# Schematic.net
KiCad netlist of a schematic drawn in Altium Designer
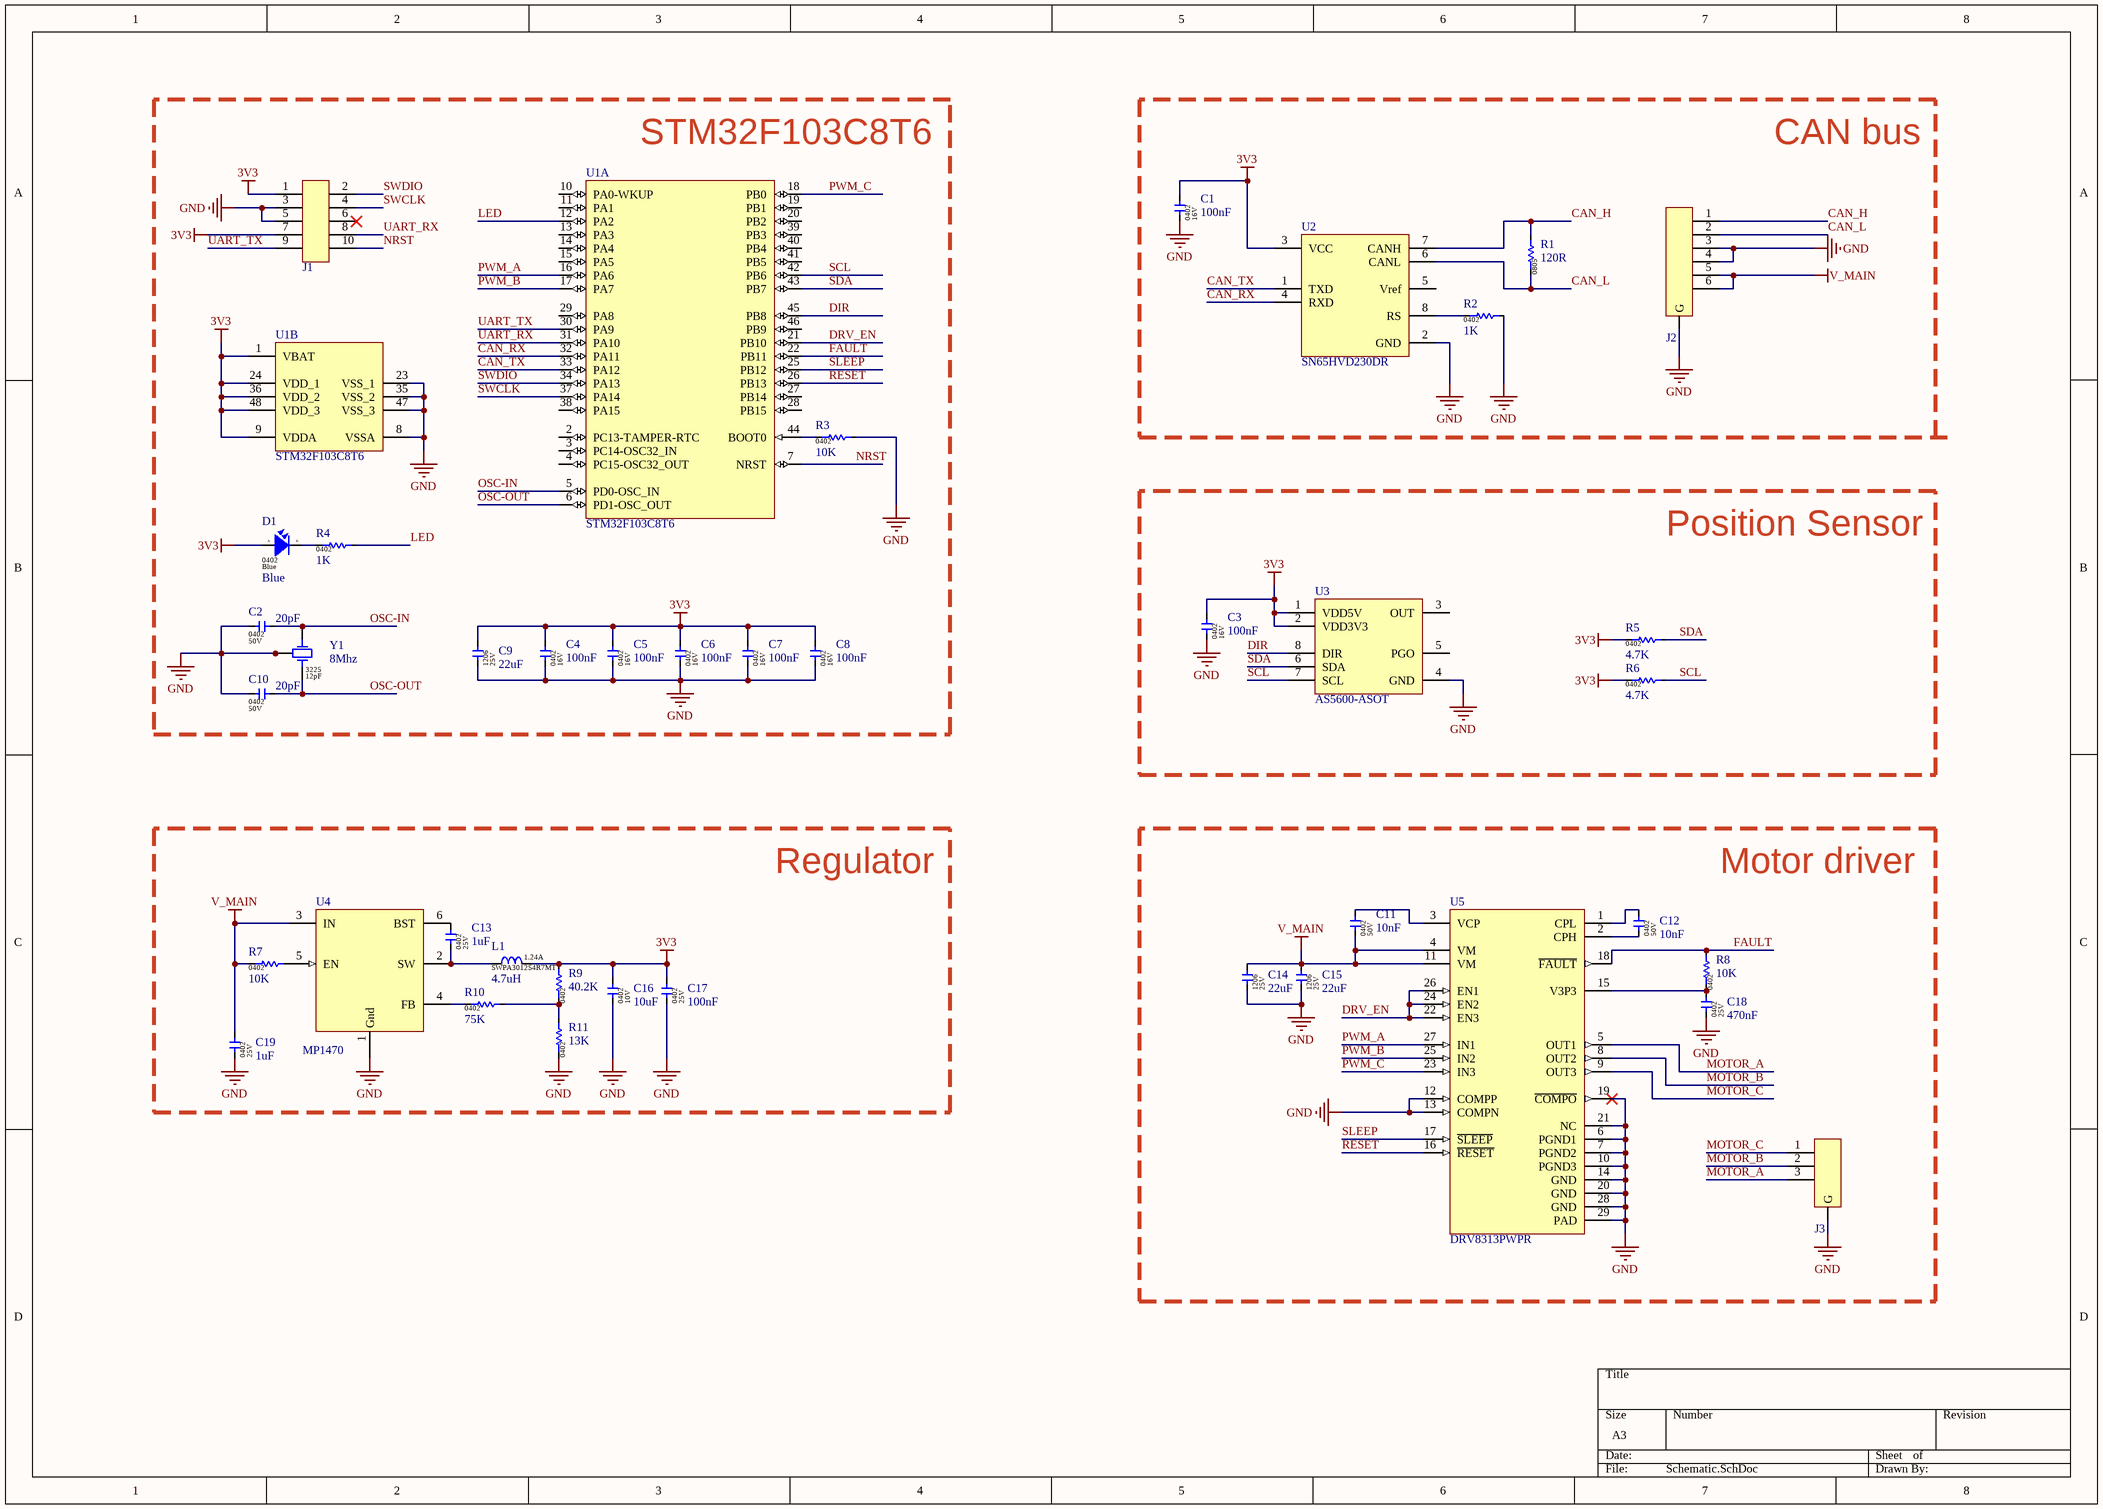
[diagram p0: Schematic.SchDoc]

(export (version "E")
  (design (tool "Eeschema 10.0.6"))
  (components
    (comp (ref "C1")
      (value "100nF")
      (footprint "CAP-0402")
      (description "100nF ±10% 16V X7R 0402 Multilayer Ceramic Capacitors MLCC - SMD/SMT RoHS")
      (fields (field (name "MANUFACTURE PART") "0402B104K160CT") (field (name "VOLTAGE") "16V"))
      (libsource (lib "Capacitor Database") (part "Cap-non-polarized"))
    )
    (comp (ref "C2")
      (value "20pF")
      (footprint "CAP-0402")
      (description "20 pF ±5% 50V Ceramic Capacitor C0G, NP0 0402 (1005 Metric)")
      (fields (field (name "MANUFACTURE PART") "CL05C200JB5NNNC") (field (name "VOLTAGE") "50V"))
      (libsource (lib "Capacitor Database") (part "Cap-non-polarized"))
    )
    (comp (ref "C3")
      (value "100nF")
      (footprint "CAP-0402")
      (description "100nF ±10% 16V X7R 0402 Multilayer Ceramic Capacitors MLCC - SMD/SMT RoHS")
      (fields (field (name "MANUFACTURE PART") "0402B104K160CT") (field (name "VOLTAGE") "16V"))
      (libsource (lib "Capacitor Database") (part "Cap-non-polarized"))
    )
    (comp (ref "C4")
      (value "100nF")
      (footprint "CAP-0402")
      (description "100nF ±10% 16V X7R 0402 Multilayer Ceramic Capacitors MLCC - SMD/SMT RoHS")
      (fields (field (name "MANUFACTURE PART") "0402B104K160CT") (field (name "VOLTAGE") "16V"))
      (libsource (lib "Capacitor Database") (part "Cap-non-polarized"))
    )
    (comp (ref "C5")
      (value "100nF")
      (footprint "CAP-0402")
      (description "100nF ±10% 16V X7R 0402 Multilayer Ceramic Capacitors MLCC - SMD/SMT RoHS")
      (fields (field (name "MANUFACTURE PART") "0402B104K160CT") (field (name "VOLTAGE") "16V"))
      (libsource (lib "Capacitor Database") (part "Cap-non-polarized"))
    )
    (comp (ref "C6")
      (value "100nF")
      (footprint "CAP-0402")
      (description "100nF ±10% 16V X7R 0402 Multilayer Ceramic Capacitors MLCC - SMD/SMT RoHS")
      (fields (field (name "MANUFACTURE PART") "0402B104K160CT") (field (name "VOLTAGE") "16V"))
      (libsource (lib "Capacitor Database") (part "Cap-non-polarized"))
    )
    (comp (ref "C7")
      (value "100nF")
      (footprint "CAP-0402")
      (description "100nF ±10% 16V X7R 0402 Multilayer Ceramic Capacitors MLCC - SMD/SMT RoHS")
      (fields (field (name "MANUFACTURE PART") "0402B104K160CT") (field (name "VOLTAGE") "16V"))
      (libsource (lib "Capacitor Database") (part "Cap-non-polarized"))
    )
    (comp (ref "C8")
      (value "100nF")
      (footprint "CAP-0402")
      (description "100nF ±10% 16V X7R 0402 Multilayer Ceramic Capacitors MLCC - SMD/SMT RoHS")
      (fields (field (name "MANUFACTURE PART") "0402B104K160CT") (field (name "VOLTAGE") "16V"))
      (libsource (lib "Capacitor Database") (part "Cap-non-polarized"))
    )
    (comp (ref "C9")
      (value "22uF")
      (footprint "CAP-1206")
      (description "X5R 25V ±10% 22uF 1206 Multilayer Ceramic Capacitors MLCC - SMD/SMT ROHS")
      (fields (field (name "MANUFACTURE PART") "CL31A226KAHNNNE") (field (name "VOLTAGE") "25V"))
      (libsource (lib "Capacitor Database") (part "Cap-non-polarized"))
    )
    (comp (ref "C10")
      (value "20pF")
      (footprint "CAP-0402")
      (description "20 pF ±5% 50V Ceramic Capacitor C0G, NP0 0402 (1005 Metric)")
      (fields (field (name "MANUFACTURE PART") "CL05C200JB5NNNC") (field (name "VOLTAGE") "50V"))
      (libsource (lib "Capacitor Database") (part "Cap-non-polarized"))
    )
    (comp (ref "C11")
      (value "10nF")
      (footprint "CAP-0402")
      (description "10nF ±5% 50V X7R 0402 Multilayer Ceramic Capacitors MLCC - SMD/SMT RoHS")
      (fields (field (name "MANUFACTURE PART") "0402B103J500CT") (field (name "VOLTAGE") "50V"))
      (libsource (lib "Capacitor Database") (part "Cap-non-polarized"))
    )
    (comp (ref "C12")
      (value "10nF")
      (footprint "CAP-0402")
      (description "10nF ±5% 50V X7R 0402 Multilayer Ceramic Capacitors MLCC - SMD/SMT RoHS")
      (fields (field (name "MANUFACTURE PART") "0402B103J500CT") (field (name "VOLTAGE") "50V"))
      (libsource (lib "Capacitor Database") (part "Cap-non-polarized"))
    )
    (comp (ref "C13")
      (value "1uF")
      (footprint "CAP-0402")
      (description "25V 1uF X5R ±10% 0402 Multilayer Ceramic Capacitors MLCC - SMD/SMT ROHS")
      (fields (field (name "MANUFACTURE PART") "0402X105K250CT") (field (name "VOLTAGE") "25V"))
      (libsource (lib "Capacitor Database") (part "Cap-non-polarized"))
    )
    (comp (ref "C14")
      (value "22uF")
      (footprint "CAP-1206")
      (description "X5R 25V ±10% 22uF 1206 Multilayer Ceramic Capacitors MLCC - SMD/SMT ROHS")
      (fields (field (name "MANUFACTURE PART") "CL31A226KAHNNNE") (field (name "VOLTAGE") "25V"))
      (libsource (lib "Capacitor Database") (part "Cap-non-polarized"))
    )
    (comp (ref "C15")
      (value "22uF")
      (footprint "CAP-1206")
      (description "X5R 25V ±10% 22uF 1206 Multilayer Ceramic Capacitors MLCC - SMD/SMT ROHS")
      (fields (field (name "MANUFACTURE PART") "CL31A226KAHNNNE") (field (name "VOLTAGE") "25V"))
      (libsource (lib "Capacitor Database") (part "Cap-non-polarized"))
    )
    (comp (ref "C16")
      (value "10uF")
      (footprint "CAP-0402")
      (description "10V 10uF X5R ±20% 0402 Multilayer Ceramic Capacitors MLCC - SMD/SMT ROHS")
      (fields (field (name "MANUFACTURE PART") "CL05A106MP5NUNC") (field (name "VOLTAGE") "10V"))
      (libsource (lib "Capacitor Database") (part "Cap-non-polarized"))
    )
    (comp (ref "C17")
      (value "100nF")
      (footprint "CAP-0402")
      (description "100nF ±10% 25V X5R 0402 Multilayer Ceramic Capacitors MLCC - SMD/SMT RoHS")
      (fields (field (name "MANUFACTURE PART") "0402X104K250CT") (field (name "VOLTAGE") "25V"))
      (libsource (lib "Capacitor Database") (part "Cap-non-polarized"))
    )
    (comp (ref "C18")
      (value "470nF")
      (footprint "CAP-0402")
      (description "470nF X5R 25V ±10% 470nF 0402 Multilayer Ceramic Capacitors MLCC - SMD/SMT ROHS")
      (fields (field (name "MANUFACTURE PART") "0402X474K250CT") (field (name "VOLTAGE") "25V"))
      (libsource (lib "Capacitor Database") (part "Cap-non-polarized"))
    )
    (comp (ref "C19")
      (value "1uF")
      (footprint "CAP-0402")
      (description "25V 1uF X5R ±10% 0402 Multilayer Ceramic Capacitors MLCC - SMD/SMT ROHS")
      (fields (field (name "MANUFACTURE PART") "0402X105K250CT") (field (name "VOLTAGE") "25V"))
      (libsource (lib "Capacitor Database") (part "Cap-non-polarized"))
    )
    (comp (ref "D1")
      (value "Blue")
      (footprint "LED-0402 BLUE")
      (description "Blue 0402 Light Emitting Diodes (LED) ROHS")
      (fields (field (name "MANUFACTURE PART") "0402-blue"))
      (libsource (lib "Led Database") (part "Led"))
    )
    (comp (ref "J1")
      (value "X1270WVS-2x05B-6TV01")
      (footprint "SMD_IDC_1.27_10P")
      (description "SMD,P=1.27mm IDC Connectors ROHS")
      (libsource (lib "Connectors, Misc") (part "Conn-10P-2x5P"))
    )
    (comp (ref "J2")
      (value "1.25T-6P-WT")
      (footprint "Conn MX1.25 (6)")
      (description "MX1.25 Header Male Pin 0.049\"(1.25mm) 6 P=1.25mm Wire To Board / Wire To Wire Connector RoHS")
      (libsource (lib "Connectors, Misc") (part "Conn-6P_PAD"))
    )
    (comp (ref "J3")
      (value "1.25T-3P-WT")
      (footprint "Conn MX1.25 (3)")
      (description "MX1.25 Header Male Pin 0.049\"(1.25mm) 3 SMD,P=1.25mm Wire To Board / Wire To Wire Connector RoHS")
      (libsource (lib "Connectors, Misc") (part "Conn-3P_PAD"))
    )
    (comp (ref "L1")
      (value "4.7uH")
      (footprint "IND-3012")
      (description "Inductor 30x30x12, 4.7±20% , 1.24A")
      (fields (field (name "MANUFACTURE PART") "SWPA3012S4R7MT"))
      (libsource (lib "Inductor Database") (part "Inductor"))
    )
    (comp (ref "R1")
      (value "120R")
      (footprint "RES-0805")
      (fields (field (name "MANUFACTURE PART") "AC0805FR-7W120RL"))
      (libsource (lib "Resistor Database") (part "Resistor"))
    )
    (comp (ref "R2")
      (value "1K")
      (footprint "RES-0402")
      (description "1kΩ ±1% 1/16W ±100ppm/℃ 0402 Chip Resistor - Surface Mount RoHS")
      (fields (field (name "MANUFACTURE PART") "WR04X1001FTL"))
      (libsource (lib "Resistor Database") (part "Resistor"))
    )
    (comp (ref "R3")
      (value "10K")
      (footprint "RES-0402")
      (description "10kΩ ±1% 1/16W ±100ppm/℃ 0402 Chip Resistor - Surface Mount RoHS")
      (fields (field (name "MANUFACTURE PART") "WR04X1002FTL"))
      (libsource (lib "Resistor Database") (part "Resistor"))
    )
    (comp (ref "R4")
      (value "1K")
      (footprint "RES-0402")
      (description "1kΩ ±1% 1/16W ±100ppm/℃ 0402 Chip Resistor - Surface Mount RoHS")
      (fields (field (name "MANUFACTURE PART") "WR04X1001FTL"))
      (libsource (lib "Resistor Database") (part "Resistor"))
    )
    (comp (ref "R5")
      (value "4.7K")
      (footprint "RES-0402")
      (description "4.7kΩ ±1% 1/16W ±100ppm/℃ 0402 Chip Resistor - Surface Mount RoHS")
      (fields (field (name "MANUFACTURE PART") "WR04X4701FTL"))
      (libsource (lib "Resistor Database") (part "Resistor"))
    )
    (comp (ref "R6")
      (value "4.7K")
      (footprint "RES-0402")
      (description "4.7kΩ ±1% 1/16W ±100ppm/℃ 0402 Chip Resistor - Surface Mount RoHS")
      (fields (field (name "MANUFACTURE PART") "WR04X4701FTL"))
      (libsource (lib "Resistor Database") (part "Resistor"))
    )
    (comp (ref "R7")
      (value "10K")
      (footprint "RES-0402")
      (description "10kΩ ±1% 1/16W ±100ppm/℃ 0402 Chip Resistor - Surface Mount RoHS")
      (fields (field (name "MANUFACTURE PART") "WR04X1002FTL"))
      (libsource (lib "Resistor Database") (part "Resistor"))
    )
    (comp (ref "R8")
      (value "10K")
      (footprint "RES-0402")
      (description "10kΩ ±1% 1/16W ±100ppm/℃ 0402 Chip Resistor - Surface Mount RoHS")
      (fields (field (name "MANUFACTURE PART") "WR04X1002FTL"))
      (libsource (lib "Resistor Database") (part "Resistor"))
    )
    (comp (ref "R9")
      (value "40.2K")
      (footprint "RES-0402")
      (description "62.5mW Thick Film Resistors ±1% 40.2kΩ 0402 Chip Resistor - Surface Mount ROHS")
      (fields (field (name "MANUFACTURE PART") "RC0402FR-0740K2L"))
      (libsource (lib "Resistor Database") (part "Resistor"))
    )
    (comp (ref "R10")
      (value "75K")
      (footprint "RES-0402")
      (description "75kΩ ±1% 1/16W ±100ppm/℃ 0402 Chip Resistor - Surface Mount RoHS")
      (fields (field (name "MANUFACTURE PART") "WR04X7502FTL"))
      (libsource (lib "Resistor Database") (part "Resistor"))
    )
    (comp (ref "R11")
      (value "13K")
      (footprint "RES-0402")
      (description "62.5mW Thick Film Resistors ±100ppm/℃ ±1% 13kΩ 0402 Chip Resistor - Surface Mount ROHS")
      (fields (field (name "MANUFACTURE PART") "RC0402FR-0713KL"))
      (libsource (lib "Resistor Database") (part "Resistor"))
    )
    (comp (ref "U1")
      (value "STM32F103C8T6")
      (footprint "ST LQFP-48 7x7MM")
      (description "32-Bit FLASH ARM® Cortex®-M3 72MHz 2V ~ 3.6V LQFP-48_7x7x05P ST Microelectronics RoHS")
      (libsource (lib "IC Database") (part "STM32F103C8T6"))
    )
    (comp (ref "U2")
      (value "SN65HVD230DR")
      (footprint "SOP-8")
      (description "3.3-V CAN Bus Transceivers")
      (libsource (lib "IC Database") (part "SN65HVD23X"))
    )
    (comp (ref "U3")
      (value "AS5600-ASOT")
      (footprint "SOP-8")
      (description "0°~360° SOP-8 Position Sensor ROHS")
      (libsource (lib "IC Database") (part "AS5600"))
    )
    (comp (ref "U4")
      (value "MP1470")
      (footprint "SOT23-6")
      (description "High-Efficiency, 2A, 16V, 500kHz Synchronous, Step-Down Converter In a 6-Pin TSOT 23")
      (libsource (lib "Regulator Database") (part "MP1470"))
    )
    (comp (ref "U5")
      (value "DRV8313PWPR")
      (footprint "TSSOP-28_PAD")
      (description "BLDC 8V~60V Parallel TSSOP-28-EP Motor Driver ICs ROHS")
      (libsource (lib "IC Database") (part "DRV8313PWPR"))
    )
    (comp (ref "Y1")
      (value "8Mhz")
      (footprint "Crystal-3225")
      (description "8MHz ±10ppm 20pF 400Ω SMD,3.2x2.5mm Crystals RoHS")
      (fields (field (name "MANUFACTURE PART") "X3S008000BK1H-U"))
      (libsource (lib "Osc Database") (part "XTAL-4 pin"))
    )
  )
  (nets
    (net (code "1") (name "/CAN_H") (class "Default")
      (node (ref "J2") (pin "1") (pinfunction "1_1") (pintype "passive"))
      (node (ref "R1") (pin "2") (pinfunction "2_2") (pintype "passive"))
      (node (ref "U2") (pin "7") (pinfunction "CANH_7") (pintype "passive"))
    )
    (net (code "2") (name "/CAN_L") (class "Default")
      (node (ref "J2") (pin "2") (pinfunction "2_2") (pintype "passive"))
      (node (ref "R1") (pin "1") (pinfunction "1_1") (pintype "passive"))
      (node (ref "U2") (pin "6") (pinfunction "CANL_6") (pintype "passive"))
    )
    (net (code "3") (name "/CAN_RX") (class "Default")
      (node (ref "U1") (pin "32") (pinfunction "PA11_32") (pintype "bidirectional"))
      (node (ref "U2") (pin "4") (pinfunction "RXD_4") (pintype "passive"))
    )
    (net (code "4") (name "/CAN_TX") (class "Default")
      (node (ref "U1") (pin "33") (pinfunction "PA12_33") (pintype "bidirectional"))
      (node (ref "U2") (pin "1") (pinfunction "TXD_1") (pintype "passive"))
    )
    (net (code "5") (name "/DIR") (class "Default")
      (node (ref "U1") (pin "45") (pinfunction "PB8_45") (pintype "bidirectional"))
      (node (ref "U3") (pin "8") (pinfunction "DIR_8") (pintype "passive"))
    )
    (net (code "6") (name "/DRV_EN") (class "Default")
      (node (ref "U1") (pin "21") (pinfunction "PB10_21") (pintype "bidirectional"))
      (node (ref "U5") (pin "22") (pinfunction "EN3_22") (pintype "input"))
      (node (ref "U5") (pin "24") (pinfunction "EN2_24") (pintype "input"))
      (node (ref "U5") (pin "26") (pinfunction "EN1_26") (pintype "input"))
    )
    (net (code "7") (name "/FAULT") (class "Default")
      (node (ref "R8") (pin "2") (pinfunction "2_2") (pintype "passive"))
      (node (ref "U1") (pin "22") (pinfunction "PB11_22") (pintype "bidirectional"))
      (node (ref "U5") (pin "18") (pinfunction "~{FAULT}_18") (pintype "output"))
    )
    (net (code "8") (name "/LED") (class "Default")
      (node (ref "R4") (pin "2") (pinfunction "2_2") (pintype "passive"))
      (node (ref "U1") (pin "12") (pinfunction "PA2_12") (pintype "bidirectional"))
    )
    (net (code "9") (name "/MOTOR_A") (class "Default")
      (node (ref "J3") (pin "3") (pinfunction "3_3") (pintype "passive"))
      (node (ref "U5") (pin "5") (pinfunction "OUT1_5") (pintype "output"))
    )
    (net (code "10") (name "/MOTOR_B") (class "Default")
      (node (ref "J3") (pin "2") (pinfunction "2_2") (pintype "passive"))
      (node (ref "U5") (pin "8") (pinfunction "OUT2_8") (pintype "output"))
    )
    (net (code "11") (name "/MOTOR_C") (class "Default")
      (node (ref "J3") (pin "1") (pinfunction "1_1") (pintype "passive"))
      (node (ref "U5") (pin "9") (pinfunction "OUT3_9") (pintype "output"))
    )
    (net (code "12") (name "/NRST") (class "Default")
      (node (ref "J1") (pin "10") (pinfunction "10_10") (pintype "passive"))
      (node (ref "U1") (pin "7") (pinfunction "NRST_7") (pintype "bidirectional"))
    )
    (net (code "13") (name "/OSC-IN") (class "Default")
      (node (ref "C2") (pin "2") (pinfunction "2_2") (pintype "passive"))
      (node (ref "U1") (pin "5") (pinfunction "PD0-OSC_IN_5") (pintype "bidirectional"))
      (node (ref "Y1") (pin "1") (pinfunction "X1_1") (pintype "passive"))
    )
    (net (code "14") (name "/OSC-OUT") (class "Default")
      (node (ref "C10") (pin "2") (pinfunction "2_2") (pintype "passive"))
      (node (ref "U1") (pin "6") (pinfunction "PD1-OSC_OUT_6") (pintype "bidirectional"))
      (node (ref "Y1") (pin "3") (pinfunction "X2_3") (pintype "passive"))
    )
    (net (code "15") (name "/PWM_A") (class "Default")
      (node (ref "U1") (pin "16") (pinfunction "PA6_16") (pintype "bidirectional"))
      (node (ref "U5") (pin "27") (pinfunction "IN1_27") (pintype "input"))
    )
    (net (code "16") (name "/PWM_B") (class "Default")
      (node (ref "U1") (pin "17") (pinfunction "PA7_17") (pintype "bidirectional"))
      (node (ref "U5") (pin "25") (pinfunction "IN2_25") (pintype "input"))
    )
    (net (code "17") (name "/PWM_C") (class "Default")
      (node (ref "U1") (pin "18") (pinfunction "PB0_18") (pintype "bidirectional"))
      (node (ref "U5") (pin "23") (pinfunction "IN3_23") (pintype "input"))
    )
    (net (code "18") (name "/RESET") (class "Default")
      (node (ref "U1") (pin "26") (pinfunction "PB13_26") (pintype "bidirectional"))
      (node (ref "U5") (pin "16") (pinfunction "~{RESET}_16") (pintype "input"))
    )
    (net (code "19") (name "/SCL") (class "Default")
      (node (ref "R6") (pin "2") (pinfunction "2_2") (pintype "passive"))
      (node (ref "U1") (pin "42") (pinfunction "PB6_42") (pintype "bidirectional"))
      (node (ref "U3") (pin "7") (pinfunction "SCL_7") (pintype "passive"))
    )
    (net (code "20") (name "/SDA") (class "Default")
      (node (ref "R5") (pin "2") (pinfunction "2_2") (pintype "passive"))
      (node (ref "U1") (pin "43") (pinfunction "PB7_43") (pintype "bidirectional"))
      (node (ref "U3") (pin "6") (pinfunction "SDA_6") (pintype "passive"))
    )
    (net (code "21") (name "/SLEEP") (class "Default")
      (node (ref "U1") (pin "25") (pinfunction "PB12_25") (pintype "bidirectional"))
      (node (ref "U5") (pin "17") (pinfunction "~{SLEEP}_17") (pintype "input"))
    )
    (net (code "22") (name "/SWCLK") (class "Default")
      (node (ref "J1") (pin "4") (pinfunction "4_4") (pintype "passive"))
      (node (ref "U1") (pin "37") (pinfunction "PA14_37") (pintype "bidirectional"))
    )
    (net (code "23") (name "/SWDIO") (class "Default")
      (node (ref "J1") (pin "2") (pinfunction "2_2") (pintype "passive"))
      (node (ref "U1") (pin "34") (pinfunction "PA13_34") (pintype "bidirectional"))
    )
    (net (code "24") (name "/UART_RX") (class "Default")
      (node (ref "J1") (pin "8") (pinfunction "8_8") (pintype "passive"))
      (node (ref "U1") (pin "31") (pinfunction "PA10_31") (pintype "bidirectional"))
    )
    (net (code "25") (name "/UART_TX") (class "Default")
      (node (ref "J1") (pin "9") (pinfunction "9_9") (pintype "passive"))
      (node (ref "U1") (pin "30") (pinfunction "PA9_30") (pintype "bidirectional"))
    )
    (net (code "26") (name "3V3") (class "Default")
      (node (ref "C1") (pin "2") (pinfunction "2_2") (pintype "passive"))
      (node (ref "C16") (pin "2") (pinfunction "2_2") (pintype "passive"))
      (node (ref "C17") (pin "2") (pinfunction "2_2") (pintype "passive"))
      (node (ref "C3") (pin "2") (pinfunction "2_2") (pintype "passive"))
      (node (ref "C4") (pin "2") (pinfunction "2_2") (pintype "passive"))
      (node (ref "C5") (pin "2") (pinfunction "2_2") (pintype "passive"))
      (node (ref "C6") (pin "2") (pinfunction "2_2") (pintype "passive"))
      (node (ref "C7") (pin "2") (pinfunction "2_2") (pintype "passive"))
      (node (ref "C8") (pin "2") (pinfunction "2_2") (pintype "passive"))
      (node (ref "C9") (pin "2") (pinfunction "2_2") (pintype "passive"))
      (node (ref "D1") (pin "2") (pinfunction "Anode_2") (pintype "passive"))
      (node (ref "J1") (pin "1") (pinfunction "1_1") (pintype "passive"))
      (node (ref "J1") (pin "7") (pinfunction "7_7") (pintype "passive"))
      (node (ref "L1") (pin "2") (pinfunction "2_2") (pintype "passive"))
      (node (ref "R5") (pin "1") (pinfunction "1_1") (pintype "passive"))
      (node (ref "R6") (pin "1") (pinfunction "1_1") (pintype "passive"))
      (node (ref "R9") (pin "2") (pinfunction "2_2") (pintype "passive"))
      (node (ref "U1") (pin "1") (pinfunction "VBAT_1") (pintype "power_in"))
      (node (ref "U1") (pin "24") (pinfunction "VDD_1_24") (pintype "power_in"))
      (node (ref "U1") (pin "36") (pinfunction "VDD_2_36") (pintype "power_in"))
      (node (ref "U1") (pin "48") (pinfunction "VDD_3_48") (pintype "power_in"))
      (node (ref "U1") (pin "9") (pinfunction "VDDA_9") (pintype "power_in"))
      (node (ref "U2") (pin "3") (pinfunction "VCC_3") (pintype "passive"))
      (node (ref "U3") (pin "1") (pinfunction "VDD5V_1") (pintype "passive"))
      (node (ref "U3") (pin "2") (pinfunction "VDD3V3_2") (pintype "passive"))
    )
    (net (code "27") (name "GND") (class "Default")
      (node (ref "C1") (pin "1") (pinfunction "1_1") (pintype "passive"))
      (node (ref "C10") (pin "1") (pinfunction "1_1") (pintype "passive"))
      (node (ref "C14") (pin "1") (pinfunction "1_1") (pintype "passive"))
      (node (ref "C15") (pin "1") (pinfunction "1_1") (pintype "passive"))
      (node (ref "C16") (pin "1") (pinfunction "1_1") (pintype "passive"))
      (node (ref "C17") (pin "1") (pinfunction "1_1") (pintype "passive"))
      (node (ref "C18") (pin "1") (pinfunction "1_1") (pintype "passive"))
      (node (ref "C19") (pin "1") (pinfunction "1_1") (pintype "passive"))
      (node (ref "C2") (pin "1") (pinfunction "1_1") (pintype "passive"))
      (node (ref "C3") (pin "1") (pinfunction "1_1") (pintype "passive"))
      (node (ref "C4") (pin "1") (pinfunction "1_1") (pintype "passive"))
      (node (ref "C5") (pin "1") (pinfunction "1_1") (pintype "passive"))
      (node (ref "C6") (pin "1") (pinfunction "1_1") (pintype "passive"))
      (node (ref "C7") (pin "1") (pinfunction "1_1") (pintype "passive"))
      (node (ref "C8") (pin "1") (pinfunction "1_1") (pintype "passive"))
      (node (ref "C9") (pin "1") (pinfunction "1_1") (pintype "passive"))
      (node (ref "J1") (pin "3") (pinfunction "3_3") (pintype "passive"))
      (node (ref "J1") (pin "5") (pinfunction "5_5") (pintype "passive"))
      (node (ref "J2") (pin "0") (pinfunction "G_0") (pintype "passive"))
      (node (ref "J2") (pin "3") (pinfunction "3_3") (pintype "passive"))
      (node (ref "J2") (pin "4") (pinfunction "4_4") (pintype "passive"))
      (node (ref "J3") (pin "0") (pinfunction "G_0") (pintype "passive"))
      (node (ref "R11") (pin "1") (pinfunction "1_1") (pintype "passive"))
      (node (ref "R2") (pin "2") (pinfunction "2_2") (pintype "passive"))
      (node (ref "R3") (pin "2") (pinfunction "2_2") (pintype "passive"))
      (node (ref "U1") (pin "23") (pinfunction "VSS_1_23") (pintype "power_in"))
      (node (ref "U1") (pin "35") (pinfunction "VSS_2_35") (pintype "power_in"))
      (node (ref "U1") (pin "47") (pinfunction "VSS_3_47") (pintype "power_in"))
      (node (ref "U1") (pin "8") (pinfunction "VSSA_8") (pintype "power_in"))
      (node (ref "U2") (pin "2") (pinfunction "GND_2") (pintype "passive"))
      (node (ref "U3") (pin "4") (pinfunction "GND_4") (pintype "passive"))
      (node (ref "U4") (pin "1") (pinfunction "Gnd_1") (pintype "passive"))
      (node (ref "U5") (pin "10") (pinfunction "PGND3_10") (pintype "passive"))
      (node (ref "U5") (pin "12") (pinfunction "COMPP_12") (pintype "input"))
      (node (ref "U5") (pin "13") (pinfunction "COMPN_13") (pintype "input"))
      (node (ref "U5") (pin "14") (pinfunction "GND_14") (pintype "passive"))
      (node (ref "U5") (pin "19") (pinfunction "~{COMPO}_19") (pintype "output"))
      (node (ref "U5") (pin "20") (pinfunction "GND_20") (pintype "passive"))
      (node (ref "U5") (pin "21") (pinfunction "NC_21") (pintype "passive"))
      (node (ref "U5") (pin "28") (pinfunction "GND_28") (pintype "passive"))
      (node (ref "U5") (pin "29") (pinfunction "PAD_29") (pintype "passive"))
      (node (ref "U5") (pin "6") (pinfunction "PGND1_6") (pintype "passive"))
      (node (ref "U5") (pin "7") (pinfunction "PGND2_7") (pintype "passive"))
      (node (ref "Y1") (pin "2") (pinfunction "GND_2") (pintype "power_in"))
      (node (ref "Y1") (pin "4") (pinfunction "GND_4") (pintype "power_in"))
    )
    (net (code "28") (name "Net-(D1-Cathode)") (class "Default")
      (node (ref "D1") (pin "1") (pinfunction "Cathode_1") (pintype "passive"))
      (node (ref "R4") (pin "1") (pinfunction "1_1") (pintype "passive"))
    )
    (net (code "29") (name "Net-(R10-Pad2)") (class "Default")
      (node (ref "R10") (pin "2") (pinfunction "2_2") (pintype "passive"))
      (node (ref "R11") (pin "2") (pinfunction "2_2") (pintype "passive"))
      (node (ref "R9") (pin "1") (pinfunction "1_1") (pintype "passive"))
    )
    (net (code "30") (name "Net-(U1A-BOOT0)") (class "Default")
      (node (ref "R3") (pin "1") (pinfunction "1_1") (pintype "passive"))
      (node (ref "U1") (pin "44") (pinfunction "BOOT0_44") (pintype "input"))
    )
    (net (code "31") (name "Net-(U2-RS)") (class "Default")
      (node (ref "R2") (pin "1") (pinfunction "1_1") (pintype "passive"))
      (node (ref "U2") (pin "8") (pinfunction "RS_8") (pintype "passive"))
    )
    (net (code "32") (name "Net-(U4-BST)") (class "Default")
      (node (ref "C13") (pin "2") (pinfunction "2_2") (pintype "passive"))
      (node (ref "U4") (pin "6") (pinfunction "BST_6") (pintype "passive"))
    )
    (net (code "33") (name "Net-(U4-EN)") (class "Default")
      (node (ref "R7") (pin "2") (pinfunction "2_2") (pintype "passive"))
      (node (ref "U4") (pin "5") (pinfunction "EN_5") (pintype "input"))
    )
    (net (code "34") (name "Net-(U4-FB)") (class "Default")
      (node (ref "R10") (pin "1") (pinfunction "1_1") (pintype "passive"))
      (node (ref "U4") (pin "4") (pinfunction "FB_4") (pintype "passive"))
    )
    (net (code "35") (name "Net-(U4-SW)") (class "Default")
      (node (ref "C13") (pin "1") (pinfunction "1_1") (pintype "passive"))
      (node (ref "L1") (pin "1") (pinfunction "1_1") (pintype "passive"))
      (node (ref "U4") (pin "2") (pinfunction "SW_2") (pintype "power_in"))
    )
    (net (code "36") (name "Net-(U5-CPH)") (class "Default")
      (node (ref "C12") (pin "1") (pinfunction "1_1") (pintype "passive"))
      (node (ref "U5") (pin "2") (pinfunction "CPH_2") (pintype "passive"))
    )
    (net (code "37") (name "Net-(U5-CPL)") (class "Default")
      (node (ref "C12") (pin "2") (pinfunction "2_2") (pintype "passive"))
      (node (ref "U5") (pin "1") (pinfunction "CPL_1") (pintype "passive"))
    )
    (net (code "38") (name "Net-(U5-V3P3)") (class "Default")
      (node (ref "C18") (pin "2") (pinfunction "2_2") (pintype "passive"))
      (node (ref "R8") (pin "1") (pinfunction "1_1") (pintype "passive"))
      (node (ref "U5") (pin "15") (pinfunction "V3P3_15") (pintype "passive"))
    )
    (net (code "39") (name "Net-(U5-VCP)") (class "Default")
      (node (ref "C11") (pin "2") (pinfunction "2_2") (pintype "passive"))
      (node (ref "U5") (pin "3") (pinfunction "VCP_3") (pintype "passive"))
    )
    (net (code "40") (name "V_MAIN") (class "Default")
      (node (ref "C11") (pin "1") (pinfunction "1_1") (pintype "passive"))
      (node (ref "C14") (pin "2") (pinfunction "2_2") (pintype "passive"))
      (node (ref "C15") (pin "2") (pinfunction "2_2") (pintype "passive"))
      (node (ref "C19") (pin "2") (pinfunction "2_2") (pintype "passive"))
      (node (ref "J2") (pin "5") (pinfunction "5_5") (pintype "passive"))
      (node (ref "J2") (pin "6") (pinfunction "6_6") (pintype "passive"))
      (node (ref "R7") (pin "1") (pinfunction "1_1") (pintype "passive"))
      (node (ref "U4") (pin "3") (pinfunction "IN_3") (pintype "power_in"))
      (node (ref "U5") (pin "11") (pinfunction "VM_11") (pintype "passive"))
      (node (ref "U5") (pin "4") (pinfunction "VM_4") (pintype "passive"))
    )
    (net (code "41") (name "unconnected-(J1-Pad6)") (class "Default")
      (node (ref "J1") (pin "6") (pinfunction "6_6") (pintype "passive+no_connect"))
    )
    (net (code "42") (name "unconnected-(U1A-PA0-WKUP-Pad10)") (class "Default")
      (node (ref "U1") (pin "10") (pinfunction "PA0-WKUP_10") (pintype "bidirectional"))
    )
    (net (code "43") (name "unconnected-(U1A-PA1-Pad11)") (class "Default")
      (node (ref "U1") (pin "11") (pinfunction "PA1_11") (pintype "bidirectional"))
    )
    (net (code "44") (name "unconnected-(U1A-PA3-Pad13)") (class "Default")
      (node (ref "U1") (pin "13") (pinfunction "PA3_13") (pintype "bidirectional"))
    )
    (net (code "45") (name "unconnected-(U1A-PA4-Pad14)") (class "Default")
      (node (ref "U1") (pin "14") (pinfunction "PA4_14") (pintype "bidirectional"))
    )
    (net (code "46") (name "unconnected-(U1A-PA5-Pad15)") (class "Default")
      (node (ref "U1") (pin "15") (pinfunction "PA5_15") (pintype "bidirectional"))
    )
    (net (code "47") (name "unconnected-(U1A-PA8-Pad29)") (class "Default")
      (node (ref "U1") (pin "29") (pinfunction "PA8_29") (pintype "bidirectional"))
    )
    (net (code "48") (name "unconnected-(U1A-PA15-Pad38)") (class "Default")
      (node (ref "U1") (pin "38") (pinfunction "PA15_38") (pintype "bidirectional"))
    )
    (net (code "49") (name "unconnected-(U1A-PB1-Pad19)") (class "Default")
      (node (ref "U1") (pin "19") (pinfunction "PB1_19") (pintype "bidirectional"))
    )
    (net (code "50") (name "unconnected-(U1A-PB2-Pad20)") (class "Default")
      (node (ref "U1") (pin "20") (pinfunction "PB2_20") (pintype "bidirectional"))
    )
    (net (code "51") (name "unconnected-(U1A-PB3-Pad39)") (class "Default")
      (node (ref "U1") (pin "39") (pinfunction "PB3_39") (pintype "bidirectional"))
    )
    (net (code "52") (name "unconnected-(U1A-PB4-Pad40)") (class "Default")
      (node (ref "U1") (pin "40") (pinfunction "PB4_40") (pintype "bidirectional"))
    )
    (net (code "53") (name "unconnected-(U1A-PB5-Pad41)") (class "Default")
      (node (ref "U1") (pin "41") (pinfunction "PB5_41") (pintype "bidirectional"))
    )
    (net (code "54") (name "unconnected-(U1A-PB9-Pad46)") (class "Default")
      (node (ref "U1") (pin "46") (pinfunction "PB9_46") (pintype "bidirectional"))
    )
    (net (code "55") (name "unconnected-(U1A-PB14-Pad27)") (class "Default")
      (node (ref "U1") (pin "27") (pinfunction "PB14_27") (pintype "bidirectional"))
    )
    (net (code "56") (name "unconnected-(U1A-PB15-Pad28)") (class "Default")
      (node (ref "U1") (pin "28") (pinfunction "PB15_28") (pintype "bidirectional"))
    )
    (net (code "57") (name "unconnected-(U1A-PC13-TAMPER-RTC-Pad2)") (class "Default")
      (node (ref "U1") (pin "2") (pinfunction "PC13-TAMPER-RTC_2") (pintype "bidirectional"))
    )
    (net (code "58") (name "unconnected-(U1A-PC14-OSC32_IN-Pad3)") (class "Default")
      (node (ref "U1") (pin "3") (pinfunction "PC14-OSC32_IN_3") (pintype "bidirectional"))
    )
    (net (code "59") (name "unconnected-(U1A-PC15-OSC32_OUT-Pad4)") (class "Default")
      (node (ref "U1") (pin "4") (pinfunction "PC15-OSC32_OUT_4") (pintype "bidirectional"))
    )
    (net (code "60") (name "unconnected-(U2-Vref-Pad5)") (class "Default")
      (node (ref "U2") (pin "5") (pinfunction "Vref_5") (pintype "passive"))
    )
    (net (code "61") (name "unconnected-(U3-OUT-Pad3)") (class "Default")
      (node (ref "U3") (pin "3") (pinfunction "OUT_3") (pintype "passive"))
    )
    (net (code "62") (name "unconnected-(U3-PGO-Pad5)") (class "Default")
      (node (ref "U3") (pin "5") (pinfunction "PGO_5") (pintype "passive"))
    )
  )
)
